# Top_Level.net
KiCad netlist of a schematic drawn in Altium Designer
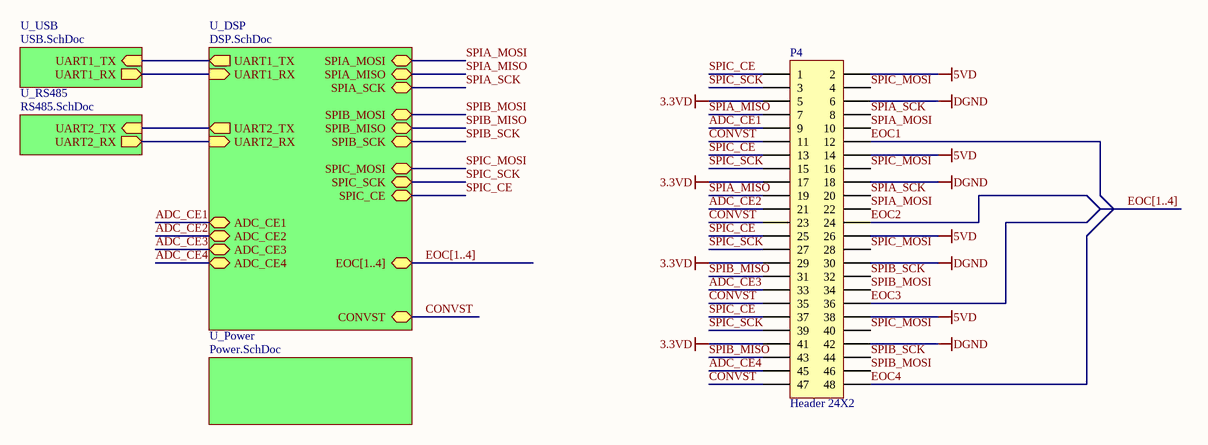
[diagram p0: Top_Level.SchDoc]

(export (version "E")
  (design (tool "Eeschema 10.0.6"))
  (components
    (comp (ref "P4")
      (value "Header 24X2")
      (footprint "HDR2X24")
      (description "Header, 24-Pin, Dual row")
      (fields (field (name "PUBLISHER") "Altium Limited"))
      (libsource (lib "Miscellaneous Connectors") (part "Header 24X2"))
    )
  )
  (nets
    (net (code "1") (name "/ADC_CE1") (class "Default")
      (node (ref "P4") (pin "9") (pinfunction "9_9") (pintype "passive"))
    )
    (net (code "2") (name "/ADC_CE2") (class "Default")
      (node (ref "P4") (pin "21") (pinfunction "21_21") (pintype "passive"))
    )
    (net (code "3") (name "/ADC_CE3") (class "Default")
      (node (ref "P4") (pin "33") (pinfunction "33_33") (pintype "passive"))
    )
    (net (code "4") (name "/ADC_CE4") (class "Default")
      (node (ref "P4") (pin "45") (pinfunction "45_45") (pintype "passive"))
    )
    (net (code "5") (name "/CONVST") (class "Default")
      (node (ref "P4") (pin "11") (pinfunction "11_11") (pintype "passive"))
      (node (ref "P4") (pin "23") (pinfunction "23_23") (pintype "passive"))
      (node (ref "P4") (pin "35") (pinfunction "35_35") (pintype "passive"))
      (node (ref "P4") (pin "47") (pinfunction "47_47") (pintype "passive"))
    )
    (net (code "6") (name "/EOC1") (class "Default")
      (node (ref "P4") (pin "12") (pinfunction "12_12") (pintype "passive"))
    )
    (net (code "7") (name "/EOC2") (class "Default")
      (node (ref "P4") (pin "24") (pinfunction "24_24") (pintype "passive"))
    )
    (net (code "8") (name "/EOC3") (class "Default")
      (node (ref "P4") (pin "36") (pinfunction "36_36") (pintype "passive"))
    )
    (net (code "9") (name "/EOC4") (class "Default")
      (node (ref "P4") (pin "48") (pinfunction "48_48") (pintype "passive"))
    )
    (net (code "11") (name "/SPIA_MISO") (class "Default")
      (node (ref "P4") (pin "19") (pinfunction "19_19") (pintype "passive"))
      (node (ref "P4") (pin "7") (pinfunction "7_7") (pintype "passive"))
    )
    (net (code "12") (name "/SPIA_MOSI") (class "Default")
      (node (ref "P4") (pin "10") (pinfunction "10_10") (pintype "passive"))
      (node (ref "P4") (pin "22") (pinfunction "22_22") (pintype "passive"))
    )
    (net (code "13") (name "/SPIA_SCK") (class "Default")
      (node (ref "P4") (pin "20") (pinfunction "20_20") (pintype "passive"))
      (node (ref "P4") (pin "8") (pinfunction "8_8") (pintype "passive"))
    )
    (net (code "14") (name "/SPIB_MISO") (class "Default")
      (node (ref "P4") (pin "31") (pinfunction "31_31") (pintype "passive"))
      (node (ref "P4") (pin "43") (pinfunction "43_43") (pintype "passive"))
    )
    (net (code "15") (name "/SPIB_MOSI") (class "Default")
      (node (ref "P4") (pin "34") (pinfunction "34_34") (pintype "passive"))
      (node (ref "P4") (pin "46") (pinfunction "46_46") (pintype "passive"))
    )
    (net (code "16") (name "/SPIB_SCK") (class "Default")
      (node (ref "P4") (pin "32") (pinfunction "32_32") (pintype "passive"))
      (node (ref "P4") (pin "44") (pinfunction "44_44") (pintype "passive"))
    )
    (net (code "17") (name "/SPIC_CE") (class "Default")
      (node (ref "P4") (pin "1") (pinfunction "1_1") (pintype "passive"))
      (node (ref "P4") (pin "13") (pinfunction "13_13") (pintype "passive"))
      (node (ref "P4") (pin "25") (pinfunction "25_25") (pintype "passive"))
      (node (ref "P4") (pin "37") (pinfunction "37_37") (pintype "passive"))
    )
    (net (code "18") (name "/SPIC_MOSI") (class "Default")
      (node (ref "P4") (pin "16") (pinfunction "16_16") (pintype "passive"))
      (node (ref "P4") (pin "28") (pinfunction "28_28") (pintype "passive"))
      (node (ref "P4") (pin "4") (pinfunction "4_4") (pintype "passive"))
      (node (ref "P4") (pin "40") (pinfunction "40_40") (pintype "passive"))
    )
    (net (code "19") (name "/SPIC_SCK") (class "Default")
      (node (ref "P4") (pin "15") (pinfunction "15_15") (pintype "passive"))
      (node (ref "P4") (pin "27") (pinfunction "27_27") (pintype "passive"))
      (node (ref "P4") (pin "3") (pinfunction "3_3") (pintype "passive"))
      (node (ref "P4") (pin "39") (pinfunction "39_39") (pintype "passive"))
    )
    (net (code "24") (name "3.3VD") (class "Default")
      (node (ref "P4") (pin "17") (pinfunction "17_17") (pintype "passive"))
      (node (ref "P4") (pin "29") (pinfunction "29_29") (pintype "passive"))
      (node (ref "P4") (pin "41") (pinfunction "41_41") (pintype "passive"))
      (node (ref "P4") (pin "5") (pinfunction "5_5") (pintype "passive"))
    )
    (net (code "25") (name "5VD") (class "Default")
      (node (ref "P4") (pin "14") (pinfunction "14_14") (pintype "passive"))
      (node (ref "P4") (pin "2") (pinfunction "2_2") (pintype "passive"))
      (node (ref "P4") (pin "26") (pinfunction "26_26") (pintype "passive"))
      (node (ref "P4") (pin "38") (pinfunction "38_38") (pintype "passive"))
    )
    (net (code "26") (name "DGND") (class "Default")
      (node (ref "P4") (pin "18") (pinfunction "18_18") (pintype "passive"))
      (node (ref "P4") (pin "30") (pinfunction "30_30") (pintype "passive"))
      (node (ref "P4") (pin "42") (pinfunction "42_42") (pintype "passive"))
      (node (ref "P4") (pin "6") (pinfunction "6_6") (pintype "passive"))
    )
  )
)
